# Sen.net
KiCad netlist of a schematic drawn in EAGLE
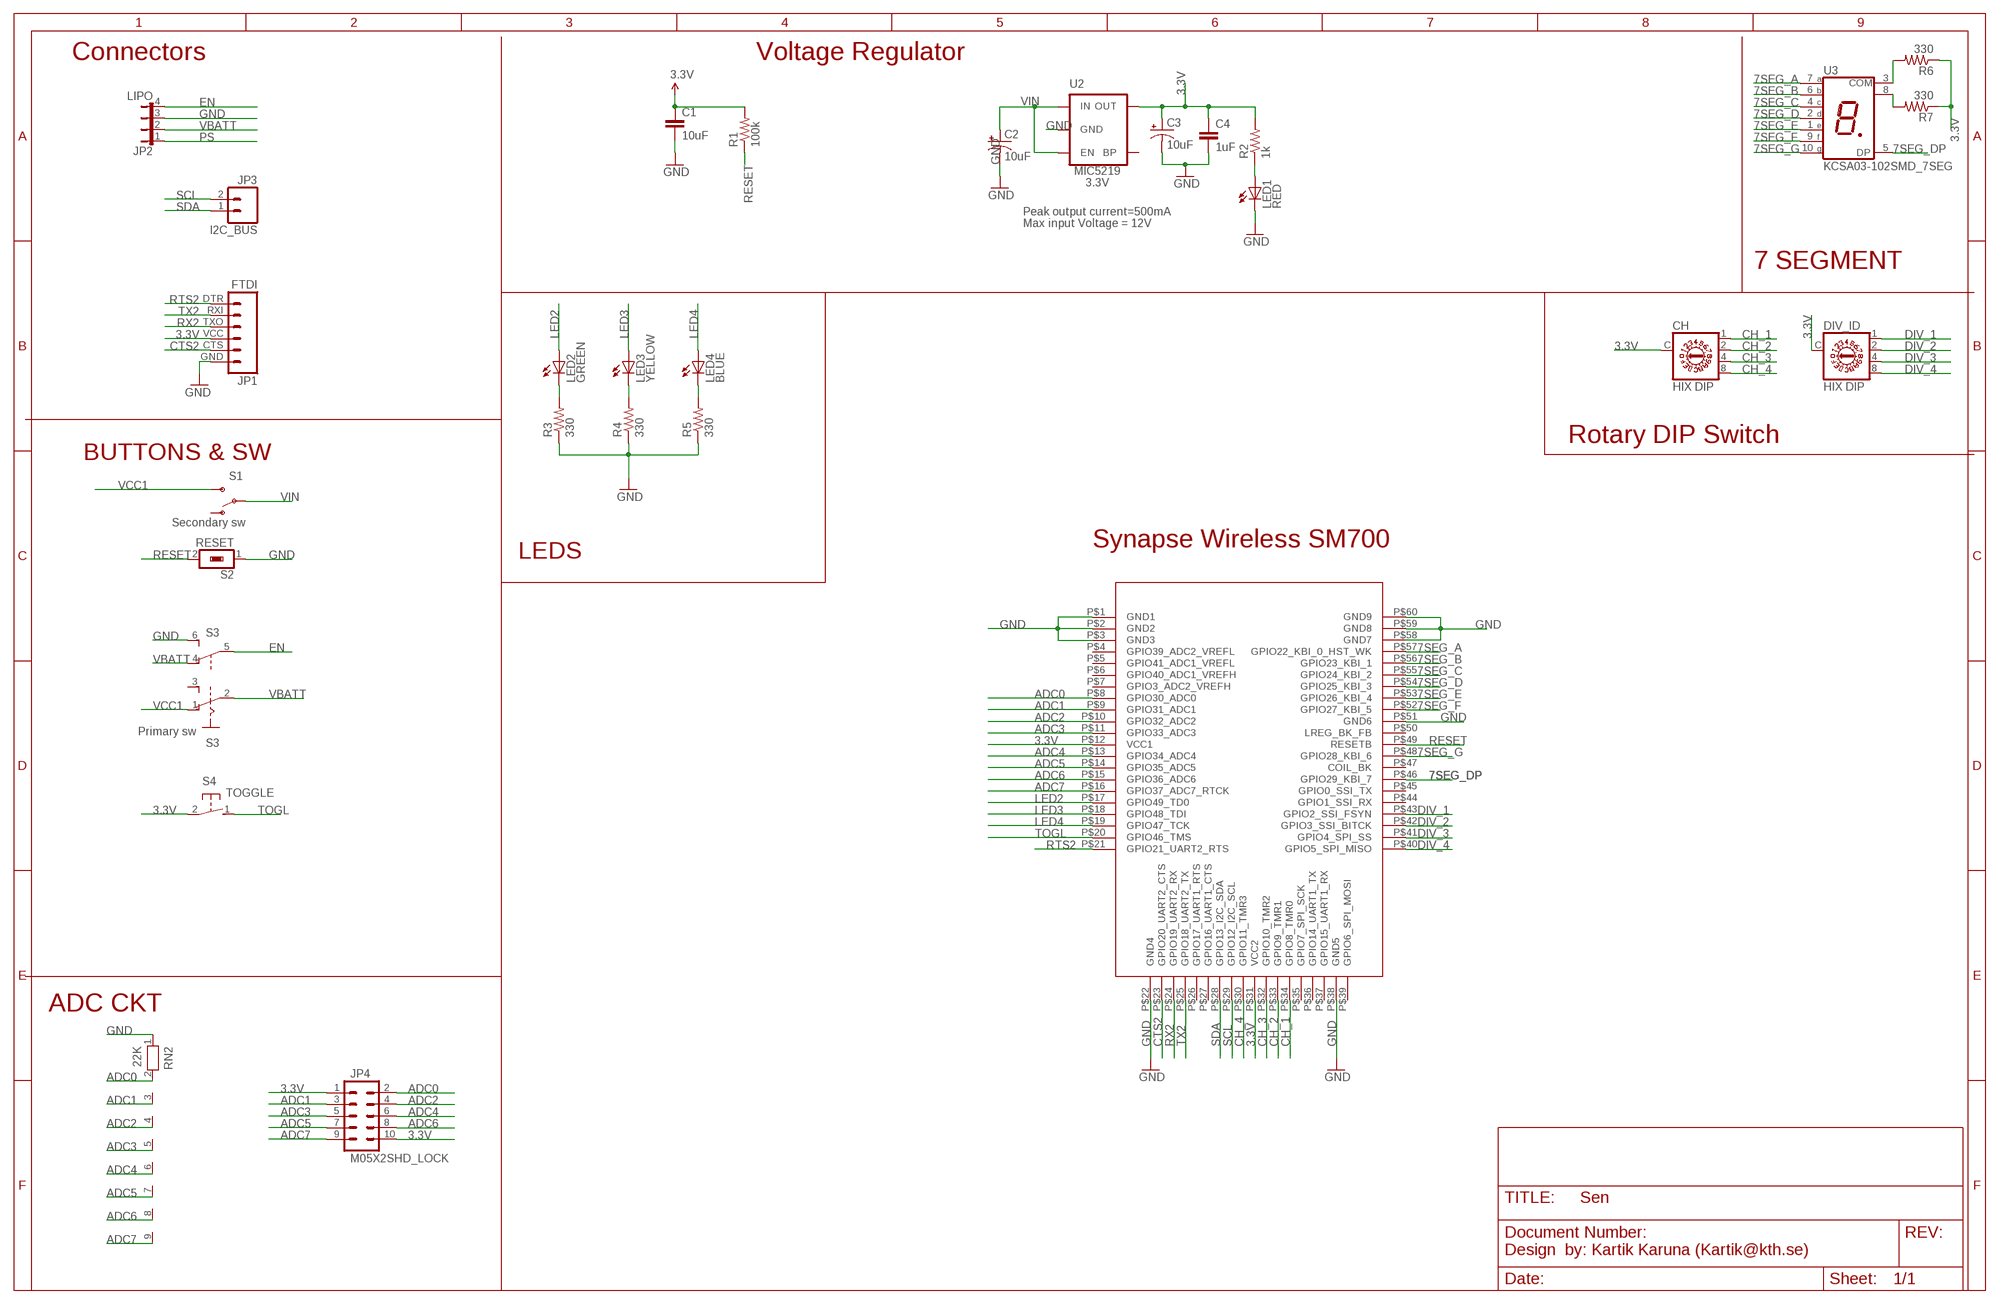
[diagram p0: schematic, sheet 1]

(export (version "E")
  (design (tool "Eeschema 10.0.6"))
  (components
    (comp (ref "C1")
      (value "10uF")
      (footprint "eagle-import:0603-CAP")
      (libsource (lib "eagle-import") (part "CAP0603-CAP"))
    )
    (comp (ref "C2")
      (value "10uF")
      (footprint "eagle-import:EIA3528")
      (libsource (lib "eagle-import") (part "CAP_POL3528"))
    )
    (comp (ref "C3")
      (value "10uF")
      (footprint "eagle-import:EIA3528")
      (libsource (lib "eagle-import") (part "CAP_POL3528"))
    )
    (comp (ref "C4")
      (value "1uF")
      (footprint "eagle-import:0402-CAP")
      (libsource (lib "eagle-import") (part "CAP0402-CAP"))
    )
    (comp (ref "CH")
      (value "HIX DIP")
      (footprint "eagle-import:A1353HEX")
      (libsource (lib "eagle-import") (part "A1353HEX"))
    )
    (comp (ref "DIV_ID")
      (value "HIX DIP")
      (footprint "eagle-import:A1353HEX")
      (libsource (lib "eagle-import") (part "A1353HEX"))
    )
    (comp (ref "JP1")
      (value "FTDI")
      (footprint "eagle-import:FTDI_BASIC")
      (libsource (lib "eagle-import") (part "FTDI_BASICPTH"))
    )
    (comp (ref "JP2")
      (value "LIPO")
      (footprint "eagle-import:JP4")
      (libsource (lib "eagle-import") (part "JP4E"))
    )
    (comp (ref "JP3")
      (value "I2C_BUS")
      (footprint "eagle-import:1X02_NO_SILK")
      (libsource (lib "eagle-import") (part "M021X02_NO_SILK"))
    )
    (comp (ref "JP4")
      (value "M05X2SHD_LOCK")
      (footprint "eagle-import:2X5-SHROUDED_LOCK")
      (libsource (lib "eagle-import") (part "M05X2SHD_LOCK"))
    )
    (comp (ref "LED1")
      (value "RED")
      (footprint "eagle-import:LED-0603")
      (libsource (lib "eagle-import") (part "LED0603"))
    )
    (comp (ref "LED2")
      (value "GREEN")
      (footprint "eagle-import:LED-0603")
      (libsource (lib "eagle-import") (part "LED0603"))
    )
    (comp (ref "LED3")
      (value "YELLOW")
      (footprint "eagle-import:LED-0603")
      (libsource (lib "eagle-import") (part "LED0603"))
    )
    (comp (ref "LED4")
      (value "BLUE")
      (footprint "eagle-import:LED-0603")
      (libsource (lib "eagle-import") (part "LED0603"))
    )
    (comp (ref "R1")
      (value "100k")
      (footprint "eagle-import:0805")
      (libsource (lib "eagle-import") (part "RESISTOR0805-RES"))
    )
    (comp (ref "R2")
      (value "1k")
      (footprint "eagle-import:0805")
      (libsource (lib "eagle-import") (part "RESISTOR0805-RES"))
    )
    (comp (ref "R3")
      (value "330")
      (footprint "eagle-import:0603-RES")
      (libsource (lib "eagle-import") (part "RESISTOR0603-RES"))
    )
    (comp (ref "R4")
      (value "330")
      (footprint "eagle-import:0603-RES")
      (libsource (lib "eagle-import") (part "RESISTOR0603-RES"))
    )
    (comp (ref "R5")
      (value "330")
      (footprint "eagle-import:0603-RES")
      (libsource (lib "eagle-import") (part "RESISTOR0603-RES"))
    )
    (comp (ref "R6")
      (value "330")
      (footprint "eagle-import:0603-RES")
      (libsource (lib "eagle-import") (part "RESISTOR0603-RES"))
    )
    (comp (ref "R7")
      (value "330")
      (footprint "eagle-import:0603-RES")
      (libsource (lib "eagle-import") (part "RESISTOR0603-RES"))
    )
    (comp (ref "RN2")
      (value "22K")
      (footprint "eagle-import:RN-9")
      (libsource (lib "eagle-import") (part "RN08"))
    )
    (comp (ref "S1")
      (value "Secondary sw")
      (footprint "eagle-import:AYZ0202")
      (libsource (lib "eagle-import") (part "SWITCH-SPDTSMD"))
    )
    (comp (ref "S2")
      (value "RESET")
      (footprint "eagle-import:TYCO_FSM")
      (libsource (lib "eagle-import") (part "TYCO_FSMSFSMSM"))
    )
    (comp (ref "S3")
      (value "Primary sw")
      (footprint "eagle-import:A68-A31")
      (libsource (lib "eagle-import") (part "A68-A31"))
    )
    (comp (ref "S4")
      (value "TOGGLE")
      (footprint "eagle-import:TYCO_FSMRACDA")
      (libsource (lib "eagle-import") (part "TYCO_FSMRACDA"))
    )
    (comp (ref "U1")
      (value "SM700PC1SMD")
      (footprint "eagle-import:SYNAPSE_SN700PC1")
      (libsource (lib "eagle-import") (part "SM700PC1SMD"))
    )
    (comp (ref "U2")
      (value "MIC5219")
      (footprint "eagle-import:SOT23-5")
      (libsource (lib "eagle-import") (part "V_REG_LDOSMD"))
    )
    (comp (ref "U3")
      (value "KCSA03-102SMD_7SEG")
      (footprint "eagle-import:SMD-7SEG")
      (libsource (lib "eagle-import") (part "KCSA03-102SMD_7SEG"))
    )
  )
  (nets
    (net (code "1") (name "/7SEG_A") (class "Default")
      (node (ref "U1") (pin "P$57") (pinfunction "GPIO22_KBI_0_HST_WK_P$57") (pintype "bidirectional"))
      (node (ref "U3") (pin "7") (pinfunction "A_7") (pintype "passive"))
    )
    (net (code "2") (name "/7SEG_B") (class "Default")
      (node (ref "U1") (pin "P$56") (pinfunction "GPIO23_KBI_1_P$56") (pintype "bidirectional"))
      (node (ref "U3") (pin "6") (pinfunction "B_6") (pintype "passive"))
    )
    (net (code "3") (name "/7SEG_C") (class "Default")
      (node (ref "U1") (pin "P$55") (pinfunction "GPIO24_KBI_2_P$55") (pintype "bidirectional"))
      (node (ref "U3") (pin "4") (pinfunction "C_4") (pintype "passive"))
    )
    (net (code "4") (name "/7SEG_D") (class "Default")
      (node (ref "U1") (pin "P$54") (pinfunction "GPIO25_KBI_3_P$54") (pintype "bidirectional"))
      (node (ref "U3") (pin "2") (pinfunction "D_2") (pintype "passive"))
    )
    (net (code "5") (name "/7SEG_DP") (class "Default")
      (node (ref "U1") (pin "P$46") (pinfunction "GPIO29_KBI_7_P$46") (pintype "bidirectional"))
      (node (ref "U3") (pin "5") (pinfunction "DP_5") (pintype "passive"))
    )
    (net (code "6") (name "/7SEG_E") (class "Default")
      (node (ref "U1") (pin "P$53") (pinfunction "GPIO26_KBI_4_P$53") (pintype "bidirectional"))
      (node (ref "U3") (pin "1") (pinfunction "E_1") (pintype "passive"))
    )
    (net (code "7") (name "/7SEG_F") (class "Default")
      (node (ref "U1") (pin "P$52") (pinfunction "GPIO27_KBI_5_P$52") (pintype "bidirectional"))
      (node (ref "U3") (pin "9") (pinfunction "F_9") (pintype "passive"))
    )
    (net (code "8") (name "/7SEG_G") (class "Default")
      (node (ref "U1") (pin "P$48") (pinfunction "GPIO28_KBI_6_P$48") (pintype "bidirectional"))
      (node (ref "U3") (pin "10") (pinfunction "G_10") (pintype "passive"))
    )
    (net (code "9") (name "/ADC0") (class "Default")
      (node (ref "JP4") (pin "2") (pinfunction "2_2") (pintype "passive"))
      (node (ref "RN2") (pin "2") (pinfunction "2_2") (pintype "passive"))
      (node (ref "U1") (pin "P$8") (pinfunction "GPIO30_ADC0_P$8") (pintype "bidirectional"))
    )
    (net (code "10") (name "/ADC1") (class "Default")
      (node (ref "JP4") (pin "3") (pinfunction "3_3") (pintype "passive"))
      (node (ref "RN2") (pin "3") (pinfunction "3_3") (pintype "passive"))
      (node (ref "U1") (pin "P$9") (pinfunction "GPIO31_ADC1_P$9") (pintype "bidirectional"))
    )
    (net (code "11") (name "/ADC2") (class "Default")
      (node (ref "JP4") (pin "4") (pinfunction "4_4") (pintype "passive"))
      (node (ref "RN2") (pin "4") (pinfunction "4_4") (pintype "passive"))
      (node (ref "U1") (pin "P$10") (pinfunction "GPIO32_ADC2_P$10") (pintype "bidirectional"))
    )
    (net (code "12") (name "/ADC3") (class "Default")
      (node (ref "JP4") (pin "5") (pinfunction "5_5") (pintype "passive"))
      (node (ref "RN2") (pin "5") (pinfunction "5_5") (pintype "passive"))
      (node (ref "U1") (pin "P$11") (pinfunction "GPIO33_ADC3_P$11") (pintype "bidirectional"))
    )
    (net (code "13") (name "/ADC4") (class "Default")
      (node (ref "JP4") (pin "6") (pinfunction "6_6") (pintype "passive"))
      (node (ref "RN2") (pin "6") (pinfunction "6_6") (pintype "passive"))
      (node (ref "U1") (pin "P$13") (pinfunction "GPIO34_ADC4_P$13") (pintype "bidirectional"))
    )
    (net (code "14") (name "/ADC5") (class "Default")
      (node (ref "JP4") (pin "7") (pinfunction "7_7") (pintype "passive"))
      (node (ref "RN2") (pin "7") (pinfunction "7_7") (pintype "passive"))
      (node (ref "U1") (pin "P$14") (pinfunction "GPIO35_ADC5_P$14") (pintype "bidirectional"))
    )
    (net (code "15") (name "/ADC6") (class "Default")
      (node (ref "JP4") (pin "8") (pinfunction "8_8") (pintype "passive"))
      (node (ref "RN2") (pin "8") (pinfunction "8_8") (pintype "passive"))
      (node (ref "U1") (pin "P$15") (pinfunction "GPIO36_ADC6_P$15") (pintype "bidirectional"))
    )
    (net (code "16") (name "/ADC7") (class "Default")
      (node (ref "JP4") (pin "9") (pinfunction "9_9") (pintype "passive"))
      (node (ref "RN2") (pin "9") (pinfunction "9_9") (pintype "passive"))
      (node (ref "U1") (pin "P$16") (pinfunction "GPIO37_ADC7_RTCK_P$16") (pintype "bidirectional"))
    )
    (net (code "17") (name "/CH_1") (class "Default")
      (node (ref "CH") (pin "1") (pinfunction "1_1") (pintype "passive"))
      (node (ref "U1") (pin "P$34") (pinfunction "GPIO8_TMR0_P$34") (pintype "bidirectional"))
    )
    (net (code "18") (name "/CH_2") (class "Default")
      (node (ref "CH") (pin "2") (pinfunction "2_2") (pintype "passive"))
      (node (ref "U1") (pin "P$33") (pinfunction "GPIO9_TMR1_P$33") (pintype "bidirectional"))
    )
    (net (code "19") (name "/CH_3") (class "Default")
      (node (ref "CH") (pin "4") (pinfunction "4_4") (pintype "passive"))
      (node (ref "U1") (pin "P$32") (pinfunction "GPIO10_TMR2_P$32") (pintype "bidirectional"))
    )
    (net (code "20") (name "/CH_4") (class "Default")
      (node (ref "CH") (pin "8") (pinfunction "8_8") (pintype "passive"))
      (node (ref "U1") (pin "P$30") (pinfunction "GPIO11_TMR3_P$30") (pintype "bidirectional"))
    )
    (net (code "21") (name "/CTS2") (class "Default")
      (node (ref "JP1") (pin "CTS") (pinfunction "5_CTS") (pintype "passive"))
      (node (ref "U1") (pin "P$23") (pinfunction "GPIO20_UART2_CTS_P$23") (pintype "bidirectional"))
    )
    (net (code "22") (name "/DIV_1") (class "Default")
      (node (ref "DIV_ID") (pin "1") (pinfunction "1_1") (pintype "passive"))
      (node (ref "U1") (pin "P$43") (pinfunction "GPIO2_SSI_FSYN_P$43") (pintype "bidirectional"))
    )
    (net (code "23") (name "/DIV_2") (class "Default")
      (node (ref "DIV_ID") (pin "2") (pinfunction "2_2") (pintype "passive"))
      (node (ref "U1") (pin "P$42") (pinfunction "GPIO3_SSI_BITCK_P$42") (pintype "bidirectional"))
    )
    (net (code "24") (name "/DIV_3") (class "Default")
      (node (ref "DIV_ID") (pin "4") (pinfunction "4_4") (pintype "passive"))
      (node (ref "U1") (pin "P$41") (pinfunction "GPIO4_SPI_SS_P$41") (pintype "bidirectional"))
    )
    (net (code "25") (name "/DIV_4") (class "Default")
      (node (ref "DIV_ID") (pin "8") (pinfunction "8_8") (pintype "passive"))
      (node (ref "U1") (pin "P$40") (pinfunction "GPIO5_SPI_MISO_P$40") (pintype "bidirectional"))
    )
    (net (code "26") (name "/EN") (class "Default")
      (node (ref "JP2") (pin "4") (pinfunction "4_4") (pintype "passive"))
      (node (ref "S3") (pin "5") (pinfunction "P_5") (pintype "passive"))
    )
    (net (code "27") (name "/LED2") (class "Default")
      (node (ref "LED2") (pin "A") (pinfunction "A_A") (pintype "passive"))
      (node (ref "U1") (pin "P$17") (pinfunction "GPIO49_TD0_P$17") (pintype "bidirectional"))
    )
    (net (code "28") (name "/LED3") (class "Default")
      (node (ref "LED3") (pin "A") (pinfunction "A_A") (pintype "passive"))
      (node (ref "U1") (pin "P$18") (pinfunction "GPIO48_TDI_P$18") (pintype "bidirectional"))
    )
    (net (code "29") (name "/LED4") (class "Default")
      (node (ref "LED4") (pin "A") (pinfunction "A_A") (pintype "passive"))
      (node (ref "U1") (pin "P$19") (pinfunction "GPIO47_TCK_P$19") (pintype "bidirectional"))
    )
    (net (code "30") (name "/PS") (class "Default")
      (node (ref "JP2") (pin "1") (pinfunction "1_1") (pintype "passive"))
    )
    (net (code "31") (name "/RESET") (class "Default")
      (node (ref "R1") (pin "1") (pinfunction "1_1") (pintype "passive"))
      (node (ref "S2") (pin "2") (pinfunction "2_2") (pintype "passive"))
      (node (ref "U1") (pin "P$49") (pinfunction "RESETB_P$49") (pintype "bidirectional"))
    )
    (net (code "32") (name "/RTS2") (class "Default")
      (node (ref "JP1") (pin "DTR") (pinfunction "1_DTR") (pintype "passive"))
      (node (ref "U1") (pin "P$21") (pinfunction "GPIO21_UART2_RTS_P$21") (pintype "bidirectional"))
    )
    (net (code "33") (name "/RX2") (class "Default")
      (node (ref "JP1") (pin "TXO") (pinfunction "3_TXO") (pintype "passive"))
      (node (ref "U1") (pin "P$24") (pinfunction "GPIO19_UART2_RX_P$24") (pintype "bidirectional"))
    )
    (net (code "34") (name "/SCL") (class "Default")
      (node (ref "JP3") (pin "2") (pinfunction "2_2") (pintype "passive"))
      (node (ref "U1") (pin "P$29") (pinfunction "GPIO12_I2C_SCL_P$29") (pintype "bidirectional"))
    )
    (net (code "35") (name "/SDA") (class "Default")
      (node (ref "JP3") (pin "1") (pinfunction "1_1") (pintype "passive"))
      (node (ref "U1") (pin "P$28") (pinfunction "GPIO13_I2C_SDA_P$28") (pintype "bidirectional"))
    )
    (net (code "36") (name "/TOGL") (class "Default")
      (node (ref "S4") (pin "1") (pinfunction "1_1") (pintype "passive"))
      (node (ref "U1") (pin "P$20") (pinfunction "GPIO46_TMS_P$20") (pintype "bidirectional"))
    )
    (net (code "37") (name "/TX2") (class "Default")
      (node (ref "JP1") (pin "RXI") (pinfunction "2_RXI") (pintype "passive"))
      (node (ref "U1") (pin "P$25") (pinfunction "GPIO18_UART2_TX_P$25") (pintype "bidirectional"))
    )
    (net (code "38") (name "/VBATT") (class "Default")
      (node (ref "JP2") (pin "2") (pinfunction "2_2") (pintype "passive"))
      (node (ref "S3") (pin "2") (pinfunction "P_2") (pintype "passive"))
      (node (ref "S3") (pin "4") (pinfunction "O_4") (pintype "passive"))
    )
    (net (code "39") (name "/VCC1") (class "Default")
      (node (ref "S1") (pin "3") (pinfunction "S_3") (pintype "passive"))
      (node (ref "S3") (pin "1") (pinfunction "O_1") (pintype "passive"))
    )
    (net (code "40") (name "/VIN") (class "Default")
      (node (ref "C2") (pin "A") (pinfunction "+_A") (pintype "passive"))
      (node (ref "S1") (pin "2") (pinfunction "P_2") (pintype "passive"))
      (node (ref "U2") (pin "1") (pinfunction "IN_1") (pintype "input"))
      (node (ref "U2") (pin "3") (pinfunction "EN_3") (pintype "input"))
    )
    (net (code "41") (name "3.3V") (class "Default")
      (node (ref "C1") (pin "1") (pinfunction "1_1") (pintype "passive"))
      (node (ref "C3") (pin "A") (pinfunction "+_A") (pintype "passive"))
      (node (ref "C4") (pin "1") (pinfunction "1_1") (pintype "passive"))
      (node (ref "CH") (pin "C") (pinfunction "C_C") (pintype "passive"))
      (node (ref "DIV_ID") (pin "C") (pinfunction "C_C") (pintype "passive"))
      (node (ref "JP1") (pin "VCC") (pinfunction "4_VCC") (pintype "passive"))
      (node (ref "JP4") (pin "1") (pinfunction "1_1") (pintype "passive"))
      (node (ref "JP4") (pin "10") (pinfunction "10_10") (pintype "passive"))
      (node (ref "R1") (pin "2") (pinfunction "2_2") (pintype "passive"))
      (node (ref "R2") (pin "2") (pinfunction "2_2") (pintype "passive"))
      (node (ref "R6") (pin "1") (pinfunction "1_1") (pintype "passive"))
      (node (ref "R7") (pin "1") (pinfunction "1_1") (pintype "passive"))
      (node (ref "S4") (pin "2") (pinfunction "2_2") (pintype "passive"))
      (node (ref "U1") (pin "P$12") (pinfunction "VCC1_P$12") (pintype "bidirectional"))
      (node (ref "U1") (pin "P$31") (pinfunction "VCC2_P$31") (pintype "bidirectional"))
      (node (ref "U2") (pin "5") (pinfunction "OUT_5") (pintype "passive"))
    )
    (net (code "42") (name "GND") (class "Default")
      (node (ref "C1") (pin "2") (pinfunction "2_2") (pintype "passive"))
      (node (ref "C2") (pin "C") (pinfunction "-_C") (pintype "passive"))
      (node (ref "C3") (pin "C") (pinfunction "-_C") (pintype "passive"))
      (node (ref "C4") (pin "2") (pinfunction "2_2") (pintype "passive"))
      (node (ref "JP1") (pin "GND") (pinfunction "6_GND") (pintype "passive"))
      (node (ref "JP2") (pin "3") (pinfunction "3_3") (pintype "passive"))
      (node (ref "LED1") (pin "C") (pinfunction "C_C") (pintype "passive"))
      (node (ref "R3") (pin "1") (pinfunction "1_1") (pintype "passive"))
      (node (ref "R4") (pin "1") (pinfunction "1_1") (pintype "passive"))
      (node (ref "R5") (pin "1") (pinfunction "1_1") (pintype "passive"))
      (node (ref "RN2") (pin "1") (pinfunction "1_1") (pintype "passive"))
      (node (ref "S2") (pin "1") (pinfunction "1_1") (pintype "passive"))
      (node (ref "S3") (pin "6") (pinfunction "S_6") (pintype "passive"))
      (node (ref "U1") (pin "P$1") (pinfunction "GND1_P$1") (pintype "bidirectional"))
      (node (ref "U1") (pin "P$2") (pinfunction "GND2_P$2") (pintype "bidirectional"))
      (node (ref "U1") (pin "P$22") (pinfunction "GND4_P$22") (pintype "bidirectional"))
      (node (ref "U1") (pin "P$3") (pinfunction "GND3_P$3") (pintype "bidirectional"))
      (node (ref "U1") (pin "P$38") (pinfunction "GND5_P$38") (pintype "bidirectional"))
      (node (ref "U1") (pin "P$51") (pinfunction "GND6_P$51") (pintype "bidirectional"))
      (node (ref "U1") (pin "P$58") (pinfunction "GND7_P$58") (pintype "bidirectional"))
      (node (ref "U1") (pin "P$59") (pinfunction "GND8_P$59") (pintype "bidirectional"))
      (node (ref "U1") (pin "P$60") (pinfunction "GND9_P$60") (pintype "bidirectional"))
      (node (ref "U2") (pin "2") (pinfunction "GND_2") (pintype "input"))
    )
    (net (code "43") (name "Net-(LED1-PadA)") (class "Default")
      (node (ref "LED1") (pin "A") (pinfunction "A_A") (pintype "passive"))
      (node (ref "R2") (pin "1") (pinfunction "1_1") (pintype "passive"))
    )
    (net (code "44") (name "Net-(LED2-PadC)") (class "Default")
      (node (ref "LED2") (pin "C") (pinfunction "C_C") (pintype "passive"))
      (node (ref "R3") (pin "2") (pinfunction "2_2") (pintype "passive"))
    )
    (net (code "45") (name "Net-(LED3-PadC)") (class "Default")
      (node (ref "LED3") (pin "C") (pinfunction "C_C") (pintype "passive"))
      (node (ref "R4") (pin "2") (pinfunction "2_2") (pintype "passive"))
    )
    (net (code "46") (name "Net-(LED4-PadC)") (class "Default")
      (node (ref "LED4") (pin "C") (pinfunction "C_C") (pintype "passive"))
      (node (ref "R5") (pin "2") (pinfunction "2_2") (pintype "passive"))
    )
    (net (code "47") (name "Net-(R6-Pad2)") (class "Default")
      (node (ref "R6") (pin "2") (pinfunction "2_2") (pintype "passive"))
      (node (ref "U3") (pin "3") (pinfunction "COM_3") (pintype "passive"))
    )
    (net (code "48") (name "Net-(R7-Pad2)") (class "Default")
      (node (ref "R7") (pin "2") (pinfunction "2_2") (pintype "passive"))
      (node (ref "U3") (pin "8") (pinfunction "COM_8") (pintype "passive"))
    )
    (net (code "49") (name "unconnected-(S1-O-Pad1)") (class "Default")
      (node (ref "S1") (pin "1") (pinfunction "O_1") (pintype "passive"))
    )
    (net (code "50") (name "unconnected-(S3A-S-Pad3)") (class "Default")
      (node (ref "S3") (pin "3") (pinfunction "S_3") (pintype "passive"))
    )
    (net (code "51") (name "unconnected-(U1-COIL_BK-PadP$47)") (class "Default")
      (node (ref "U1") (pin "P$47") (pinfunction "COIL_BK_P$47") (pintype "bidirectional"))
    )
    (net (code "52") (name "unconnected-(U1-GPIO0_SSI_TX-PadP$45)") (class "Default")
      (node (ref "U1") (pin "P$45") (pinfunction "GPIO0_SSI_TX_P$45") (pintype "bidirectional"))
    )
    (net (code "53") (name "unconnected-(U1-GPIO1_SSI_RX-PadP$44)") (class "Default")
      (node (ref "U1") (pin "P$44") (pinfunction "GPIO1_SSI_RX_P$44") (pintype "bidirectional"))
    )
    (net (code "54") (name "unconnected-(U1-GPIO3_ADC2_VREFH-PadP$7)") (class "Default")
      (node (ref "U1") (pin "P$7") (pinfunction "GPIO3_ADC2_VREFH_P$7") (pintype "bidirectional"))
    )
    (net (code "55") (name "unconnected-(U1-GPIO6_SPI_MOSI-PadP$39)") (class "Default")
      (node (ref "U1") (pin "P$39") (pinfunction "GPIO6_SPI_MOSI_P$39") (pintype "bidirectional"))
    )
    (net (code "56") (name "unconnected-(U1-GPIO7_SPI_SCK-PadP$35)") (class "Default")
      (node (ref "U1") (pin "P$35") (pinfunction "GPIO7_SPI_SCK_P$35") (pintype "bidirectional"))
    )
    (net (code "57") (name "unconnected-(U1-GPIO14_UART1_TX-PadP$36)") (class "Default")
      (node (ref "U1") (pin "P$36") (pinfunction "GPIO14_UART1_TX_P$36") (pintype "bidirectional"))
    )
    (net (code "58") (name "unconnected-(U1-GPIO15_UART1_RX-PadP$37)") (class "Default")
      (node (ref "U1") (pin "P$37") (pinfunction "GPIO15_UART1_RX_P$37") (pintype "bidirectional"))
    )
    (net (code "59") (name "unconnected-(U1-GPIO16_UART1_CTS-PadP$27)") (class "Default")
      (node (ref "U1") (pin "P$27") (pinfunction "GPIO16_UART1_CTS_P$27") (pintype "bidirectional"))
    )
    (net (code "60") (name "unconnected-(U1-GPIO17_UART1_RTS-PadP$26)") (class "Default")
      (node (ref "U1") (pin "P$26") (pinfunction "GPIO17_UART1_RTS_P$26") (pintype "bidirectional"))
    )
    (net (code "61") (name "unconnected-(U1-GPIO39_ADC2_VREFL-PadP$4)") (class "Default")
      (node (ref "U1") (pin "P$4") (pinfunction "GPIO39_ADC2_VREFL_P$4") (pintype "bidirectional"))
    )
    (net (code "62") (name "unconnected-(U1-GPIO40_ADC1_VREFH-PadP$6)") (class "Default")
      (node (ref "U1") (pin "P$6") (pinfunction "GPIO40_ADC1_VREFH_P$6") (pintype "bidirectional"))
    )
    (net (code "63") (name "unconnected-(U1-GPIO41_ADC1_VREFL-PadP$5)") (class "Default")
      (node (ref "U1") (pin "P$5") (pinfunction "GPIO41_ADC1_VREFL_P$5") (pintype "bidirectional"))
    )
    (net (code "64") (name "unconnected-(U1-LREG_BK_FB-PadP$50)") (class "Default")
      (node (ref "U1") (pin "P$50") (pinfunction "LREG_BK_FB_P$50") (pintype "bidirectional"))
    )
    (net (code "65") (name "unconnected-(U2-BP-Pad4)") (class "Default")
      (node (ref "U2") (pin "4") (pinfunction "BP_4") (pintype "input"))
    )
  )
)
